# CON_ATA_35.net
KiCad netlist of a schematic drawn in Altium Designer
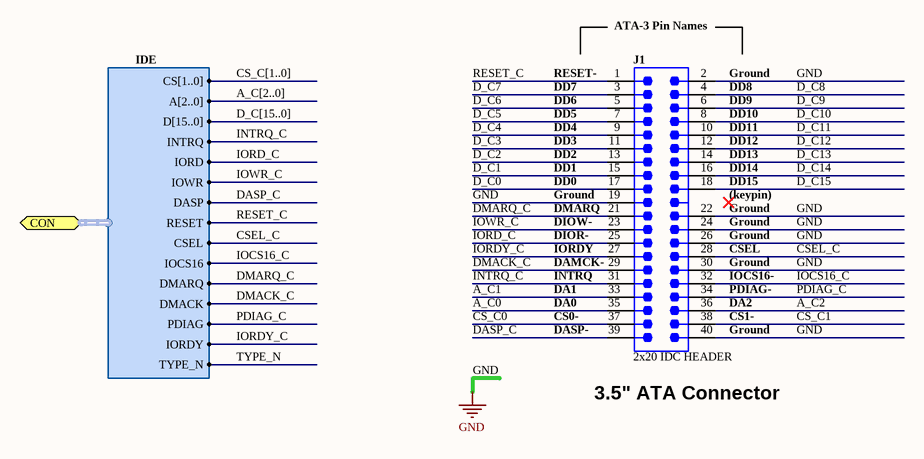
[diagram p0: CON_ATA_35.SchDoc]

(export (version "E")
  (design (tool "Eeschema 10.0.6"))
  (components
    (comp (ref "J1")
      (value "2x20 IDC HEADER")
      (footprint "918540x324")
      (description "Header, Box 2 x 20 Pin Vertical 2.54mm Pitch")
      (libsource (lib "AltiumDesignLibrary") (part "CON-IDC-2x20-M-STR"))
    )
  )
  (nets
    (net (code "2") (name "/A_C0") (class "Default")
      (node (ref "J1") (pin "35") (pinfunction "35_35") (pintype "passive"))
    )
    (net (code "3") (name "/A_C1") (class "Default")
      (node (ref "J1") (pin "33") (pinfunction "33_33") (pintype "passive"))
    )
    (net (code "4") (name "/A_C2") (class "Default")
      (node (ref "J1") (pin "36") (pinfunction "36_36") (pintype "passive"))
    )
    (net (code "6") (name "/CSEL_C") (class "Default")
      (node (ref "J1") (pin "28") (pinfunction "28_28") (pintype "passive"))
    )
    (net (code "7") (name "/CS_C0") (class "Default")
      (node (ref "J1") (pin "37") (pinfunction "37_37") (pintype "passive"))
    )
    (net (code "8") (name "/CS_C1") (class "Default")
      (node (ref "J1") (pin "38") (pinfunction "38_38") (pintype "passive"))
    )
    (net (code "10") (name "/DASP_C") (class "Default")
      (node (ref "J1") (pin "39") (pinfunction "39_39") (pintype "passive"))
    )
    (net (code "11") (name "/DMACK_C") (class "Default")
      (node (ref "J1") (pin "29") (pinfunction "29_29") (pintype "passive"))
    )
    (net (code "12") (name "/DMARQ_C") (class "Default")
      (node (ref "J1") (pin "21") (pinfunction "21_21") (pintype "passive"))
    )
    (net (code "13") (name "/D_C0") (class "Default")
      (node (ref "J1") (pin "17") (pinfunction "17_17") (pintype "passive"))
    )
    (net (code "14") (name "/D_C1") (class "Default")
      (node (ref "J1") (pin "15") (pinfunction "15_15") (pintype "passive"))
    )
    (net (code "15") (name "/D_C2") (class "Default")
      (node (ref "J1") (pin "13") (pinfunction "13_13") (pintype "passive"))
    )
    (net (code "16") (name "/D_C3") (class "Default")
      (node (ref "J1") (pin "11") (pinfunction "11_11") (pintype "passive"))
    )
    (net (code "17") (name "/D_C4") (class "Default")
      (node (ref "J1") (pin "9") (pinfunction "9_9") (pintype "passive"))
    )
    (net (code "18") (name "/D_C5") (class "Default")
      (node (ref "J1") (pin "7") (pinfunction "7_7") (pintype "passive"))
    )
    (net (code "19") (name "/D_C6") (class "Default")
      (node (ref "J1") (pin "5") (pinfunction "5_5") (pintype "passive"))
    )
    (net (code "20") (name "/D_C7") (class "Default")
      (node (ref "J1") (pin "3") (pinfunction "3_3") (pintype "passive"))
    )
    (net (code "21") (name "/D_C8") (class "Default")
      (node (ref "J1") (pin "4") (pinfunction "4_4") (pintype "passive"))
    )
    (net (code "22") (name "/D_C9") (class "Default")
      (node (ref "J1") (pin "6") (pinfunction "6_6") (pintype "passive"))
    )
    (net (code "23") (name "/D_C10") (class "Default")
      (node (ref "J1") (pin "8") (pinfunction "8_8") (pintype "passive"))
    )
    (net (code "24") (name "/D_C11") (class "Default")
      (node (ref "J1") (pin "10") (pinfunction "10_10") (pintype "passive"))
    )
    (net (code "25") (name "/D_C12") (class "Default")
      (node (ref "J1") (pin "12") (pinfunction "12_12") (pintype "passive"))
    )
    (net (code "26") (name "/D_C13") (class "Default")
      (node (ref "J1") (pin "14") (pinfunction "14_14") (pintype "passive"))
    )
    (net (code "27") (name "/D_C14") (class "Default")
      (node (ref "J1") (pin "16") (pinfunction "16_16") (pintype "passive"))
    )
    (net (code "28") (name "/D_C15") (class "Default")
      (node (ref "J1") (pin "18") (pinfunction "18_18") (pintype "passive"))
    )
    (net (code "30") (name "/INTRQ_C") (class "Default")
      (node (ref "J1") (pin "31") (pinfunction "31_31") (pintype "passive"))
    )
    (net (code "31") (name "/IOCS16_C") (class "Default")
      (node (ref "J1") (pin "32") (pinfunction "32_32") (pintype "passive"))
    )
    (net (code "32") (name "/IORDY_C") (class "Default")
      (node (ref "J1") (pin "27") (pinfunction "27_27") (pintype "passive"))
    )
    (net (code "33") (name "/IORD_C") (class "Default")
      (node (ref "J1") (pin "25") (pinfunction "25_25") (pintype "passive"))
    )
    (net (code "34") (name "/IOWR_C") (class "Default")
      (node (ref "J1") (pin "23") (pinfunction "23_23") (pintype "passive"))
    )
    (net (code "35") (name "/PDIAG_C") (class "Default")
      (node (ref "J1") (pin "34") (pinfunction "34_34") (pintype "passive"))
    )
    (net (code "36") (name "/RESET_C") (class "Default")
      (node (ref "J1") (pin "1") (pinfunction "1_1") (pintype "passive"))
    )
    (net (code "39") (name "GND") (class "Default")
      (node (ref "J1") (pin "19") (pinfunction "19_19") (pintype "passive"))
      (node (ref "J1") (pin "2") (pinfunction "2_2") (pintype "passive"))
      (node (ref "J1") (pin "22") (pinfunction "22_22") (pintype "passive"))
      (node (ref "J1") (pin "24") (pinfunction "24_24") (pintype "passive"))
      (node (ref "J1") (pin "26") (pinfunction "26_26") (pintype "passive"))
      (node (ref "J1") (pin "30") (pinfunction "30_30") (pintype "passive"))
      (node (ref "J1") (pin "40") (pinfunction "40_40") (pintype "passive"))
    )
  )
)
